# slaveMeteo.net
KiCad netlist of a schematic drawn in EAGLE
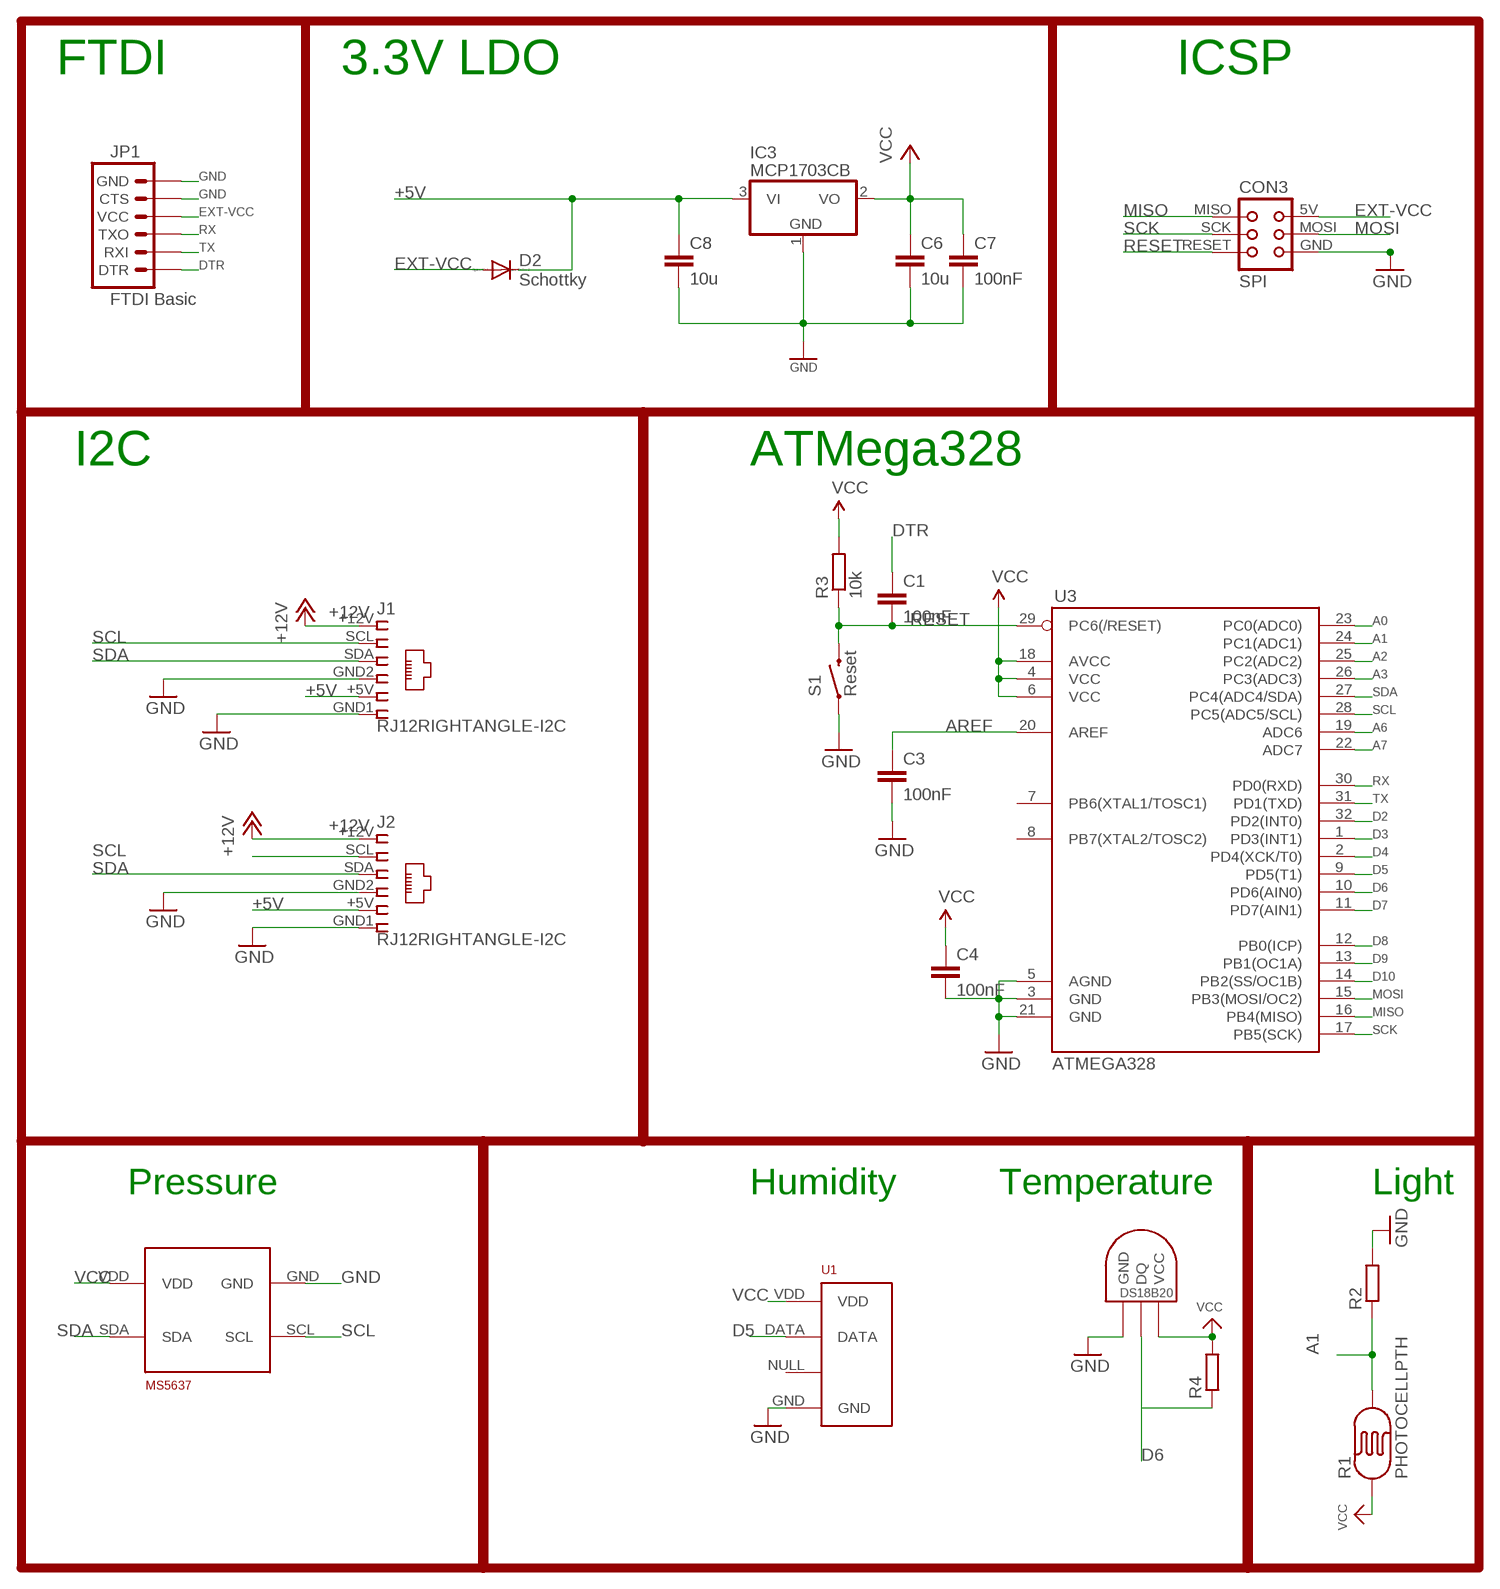
[diagram p0: schematic, sheet 1]

(export (version "E")
  (design (tool "Eeschema 10.0.6"))
  (components
    (comp (ref "C1")
      (value "100nF")
      (footprint "eagle-import:C0805K")
      (fields (field (name "MPN") "80-C1206C104K5R"))
      (libsource (lib "eagle-import") (part "C-EUC0805K"))
    )
    (comp (ref "C3")
      (value "100nF")
      (footprint "eagle-import:C0805K")
      (fields (field (name "MPN") "80-C1206C104K5R"))
      (libsource (lib "eagle-import") (part "C-EUC0805K"))
    )
    (comp (ref "C4")
      (value "100nF")
      (footprint "eagle-import:C0805K")
      (fields (field (name "MPN") "80-C1206C104K5R"))
      (libsource (lib "eagle-import") (part "C-EUC0805K"))
    )
    (comp (ref "C6")
      (value "10u")
      (footprint "eagle-import:C0805K")
      (fields (field (name "MPN") "77-VJ1206V106ZXQTBC"))
      (libsource (lib "eagle-import") (part "C-EUC0805K"))
    )
    (comp (ref "C7")
      (value "100nF")
      (footprint "eagle-import:C0805K")
      (fields (field (name "MPN") "80-C1206C104K5R"))
      (libsource (lib "eagle-import") (part "C-EUC0805K"))
    )
    (comp (ref "C8")
      (value "10u")
      (footprint "eagle-import:C0805K")
      (fields (field (name "MPN") "77-VJ1206V106ZXQTBC"))
      (libsource (lib "eagle-import") (part "C-EUC0805K"))
    )
    (comp (ref "CON3")
      (value "SPI")
      (footprint "eagle-import:TC2030-MCP")
      (libsource (lib "eagle-import") (part "TINYISPTAG"))
    )
    (comp (ref "D2")
      (value "Schottky")
      (footprint "eagle-import:SOD123")
      (fields (field (name "MPN") "621-1N5819HW-F"))
      (libsource (lib "eagle-import") (part "MBR0520LT"))
    )
    (comp (ref "IC3")
      (value "MCP1703CB")
      (footprint "eagle-import:SOT23")
      (libsource (lib "eagle-import") (part "MCP1703CB"))
    )
    (comp (ref "J1")
      (value "RJ12RIGHTANGLE-I2C")
      (footprint "eagle-import:RJ12-RIGHTANGLE-I2C")
      (libsource (lib "eagle-import") (part "RJ12RIGHTANGLE-I2C"))
    )
    (comp (ref "J2")
      (value "RJ12RIGHTANGLE-I2C")
      (footprint "eagle-import:RJ12-RIGHTANGLE-I2C")
      (libsource (lib "eagle-import") (part "RJ12RIGHTANGLE-I2C"))
    )
    (comp (ref "JP1")
      (value "FTDI Basic")
      (footprint "eagle-import:1X06")
      (libsource (lib "eagle-import") (part "ARDUINO_SERIAL_PROGRAMPTH"))
    )
    (comp (ref "R1")
      (value "PHOTOCELLPTH")
      (footprint "eagle-import:PHOTOCELL")
      (libsource (lib "eagle-import") (part "PHOTOCELLPTH"))
    )
    (comp (ref "R2")
      (value "R-EU_R0805")
      (footprint "eagle-import:R0805")
      (libsource (lib "eagle-import") (part "resistor_348_R-EU_R0805"))
    )
    (comp (ref "R3")
      (value "10k")
      (footprint "eagle-import:R0805")
      (libsource (lib "eagle-import") (part "R-EU_R0805"))
    )
    (comp (ref "R4")
      (value "R-EU_R0805")
      (footprint "eagle-import:R0805")
      (libsource (lib "eagle-import") (part "resistor_348_R-EU_R0805"))
    )
    (comp (ref "S1")
      (value "Reset")
      (footprint "eagle-import:TACTILE-SWITCH-SMD-ALT01")
      (libsource (lib "eagle-import") (part "SWITCH-MOMENTARY-2SMD-ALT01"))
    )
    (comp (ref "U$1")
      (value "DS1820TO92")
      (footprint "eagle-import:DS1820")
      (libsource (lib "eagle-import") (part "DS1820TO92"))
    )
    (comp (ref "U$19")
      (value "MS5637")
      (footprint "eagle-import:MS5637")
      (libsource (lib "eagle-import") (part "MS5637"))
    )
    (comp (ref "U1")
      (value "RHT03_DHT-22_AM2302RA")
      (footprint "eagle-import:RHT03_DHT-22_RA")
      (libsource (lib "eagle-import") (part "RHT03_DHT-22_AM2302RA"))
    )
    (comp (ref "U3")
      (value "ATMEGA328")
      (footprint "eagle-import:TQFP32-08")
      (libsource (lib "eagle-import") (part "ATMEGA168"))
    )
  )
  (nets
    (net (code "1") (name "+12V") (class "Default")
      (node (ref "J1") (pin "+12V") (pinfunction "1_+12V") (pintype "bidirectional"))
      (node (ref "J2") (pin "+12V") (pinfunction "1_+12V") (pintype "bidirectional"))
    )
    (net (code "2") (name "/+5V") (class "Default")
      (node (ref "C8") (pin "1") (pinfunction "1_1") (pintype "passive"))
      (node (ref "D2") (pin "C") (pinfunction "C_C") (pintype "passive"))
      (node (ref "IC3") (pin "3") (pinfunction "VI_3") (pintype "input"))
      (node (ref "J1") (pin "+5V") (pinfunction "5_+5V") (pintype "bidirectional"))
      (node (ref "J2") (pin "+5V") (pinfunction "5_+5V") (pintype "bidirectional"))
    )
    (net (code "3") (name "/A0") (class "Default")
      (node (ref "U3") (pin "23") (pinfunction "PC0(ADC0)_23") (pintype "bidirectional"))
    )
    (net (code "4") (name "/A1") (class "Default")
      (node (ref "R1") (pin "2") (pinfunction "P$2_2") (pintype "bidirectional"))
      (node (ref "R2") (pin "1") (pinfunction "1_1") (pintype "passive"))
      (node (ref "U3") (pin "24") (pinfunction "PC1(ADC1)_24") (pintype "bidirectional"))
    )
    (net (code "5") (name "/A2") (class "Default")
      (node (ref "U3") (pin "25") (pinfunction "PC2(ADC2)_25") (pintype "bidirectional"))
    )
    (net (code "6") (name "/A3") (class "Default")
      (node (ref "U3") (pin "26") (pinfunction "PC3(ADC3)_26") (pintype "bidirectional"))
    )
    (net (code "7") (name "/A6") (class "Default")
      (node (ref "U3") (pin "19") (pinfunction "ADC6_19") (pintype "bidirectional"))
    )
    (net (code "8") (name "/A7") (class "Default")
      (node (ref "U3") (pin "22") (pinfunction "ADC7_22") (pintype "bidirectional"))
    )
    (net (code "9") (name "/AREF") (class "Default")
      (node (ref "C3") (pin "1") (pinfunction "1_1") (pintype "passive"))
      (node (ref "U3") (pin "20") (pinfunction "AREF_20") (pintype "bidirectional"))
    )
    (net (code "10") (name "/D2") (class "Default")
      (node (ref "U3") (pin "32") (pinfunction "PD2(INT0)_32") (pintype "bidirectional"))
    )
    (net (code "11") (name "/D3") (class "Default")
      (node (ref "U3") (pin "1") (pinfunction "PD3(INT1)_1") (pintype "bidirectional"))
    )
    (net (code "12") (name "/D4") (class "Default")
      (node (ref "U3") (pin "2") (pinfunction "PD4(XCK/T0)_2") (pintype "bidirectional"))
    )
    (net (code "13") (name "/D5") (class "Default")
      (node (ref "U1") (pin "DATA") (pinfunction "DATA_DATA") (pintype "bidirectional"))
      (node (ref "U3") (pin "9") (pinfunction "PD5(T1)_9") (pintype "bidirectional"))
    )
    (net (code "14") (name "/D6") (class "Default")
      (node (ref "R4") (pin "1") (pinfunction "1_1") (pintype "passive"))
      (node (ref "U$1") (pin "DQ") (pinfunction "DQ_DQ") (pintype "bidirectional"))
      (node (ref "U3") (pin "10") (pinfunction "PD6(AIN0)_10") (pintype "bidirectional"))
    )
    (net (code "15") (name "/D7") (class "Default")
      (node (ref "U3") (pin "11") (pinfunction "PD7(AIN1)_11") (pintype "bidirectional"))
    )
    (net (code "16") (name "/D8") (class "Default")
      (node (ref "U3") (pin "12") (pinfunction "PB0(ICP)_12") (pintype "bidirectional"))
    )
    (net (code "17") (name "/D9") (class "Default")
      (node (ref "U3") (pin "13") (pinfunction "PB1(OC1A)_13") (pintype "bidirectional"))
    )
    (net (code "18") (name "/D10") (class "Default")
      (node (ref "U3") (pin "14") (pinfunction "PB2(SS/OC1B)_14") (pintype "bidirectional"))
    )
    (net (code "19") (name "/DTR") (class "Default")
      (node (ref "C1") (pin "1") (pinfunction "1_1") (pintype "passive"))
      (node (ref "JP1") (pin "1") (pinfunction "DTR_1") (pintype "passive"))
    )
    (net (code "20") (name "/EXT-VCC") (class "Default")
      (node (ref "CON3") (pin "5V") (pinfunction "VCC_5V") (pintype "passive"))
      (node (ref "D2") (pin "A") (pinfunction "A_A") (pintype "passive"))
      (node (ref "JP1") (pin "4") (pinfunction "VCC_4") (pintype "passive"))
    )
    (net (code "21") (name "/MISO") (class "Default")
      (node (ref "CON3") (pin "MISO") (pinfunction "MISO_MISO") (pintype "passive"))
      (node (ref "U3") (pin "16") (pinfunction "PB4(MISO)_16") (pintype "bidirectional"))
    )
    (net (code "22") (name "/MOSI") (class "Default")
      (node (ref "CON3") (pin "MOSI") (pinfunction "MOSI_MOSI") (pintype "passive"))
      (node (ref "U3") (pin "15") (pinfunction "PB3(MOSI/OC2)_15") (pintype "bidirectional"))
    )
    (net (code "23") (name "/RESET") (class "Default")
      (node (ref "C1") (pin "2") (pinfunction "2_2") (pintype "passive"))
      (node (ref "CON3") (pin "RESET") (pinfunction "RESET_RESET") (pintype "passive"))
      (node (ref "R3") (pin "1") (pinfunction "1_1") (pintype "passive"))
      (node (ref "S1") (pin "3") (pinfunction "2_3") (pintype "passive"))
      (node (ref "S1") (pin "4") (pinfunction "2_4") (pintype "passive"))
      (node (ref "U3") (pin "29") (pinfunction "PC6(/RESET)_29") (pintype "bidirectional"))
    )
    (net (code "24") (name "/RX") (class "Default")
      (node (ref "JP1") (pin "3") (pinfunction "TXO_3") (pintype "passive"))
      (node (ref "U3") (pin "30") (pinfunction "PD0(RXD)_30") (pintype "bidirectional"))
    )
    (net (code "25") (name "/SCK") (class "Default")
      (node (ref "CON3") (pin "SCK") (pinfunction "SCK_SCK") (pintype "passive"))
      (node (ref "U3") (pin "17") (pinfunction "PB5(SCK)_17") (pintype "bidirectional"))
    )
    (net (code "26") (name "/SCL") (class "Default")
      (node (ref "J1") (pin "SCL") (pinfunction "2_SCL") (pintype "bidirectional"))
      (node (ref "J2") (pin "SCL") (pinfunction "2_SCL") (pintype "bidirectional"))
      (node (ref "U$19") (pin "SCL") (pinfunction "SCL_SCL") (pintype "bidirectional"))
      (node (ref "U3") (pin "28") (pinfunction "PC5(ADC5/SCL)_28") (pintype "bidirectional"))
    )
    (net (code "27") (name "/SDA") (class "Default")
      (node (ref "J1") (pin "SDA") (pinfunction "3_SDA") (pintype "bidirectional"))
      (node (ref "J2") (pin "SDA") (pinfunction "3_SDA") (pintype "bidirectional"))
      (node (ref "U$19") (pin "SDA") (pinfunction "SDA_SDA") (pintype "bidirectional"))
      (node (ref "U3") (pin "27") (pinfunction "PC4(ADC4/SDA)_27") (pintype "bidirectional"))
    )
    (net (code "28") (name "/TX") (class "Default")
      (node (ref "JP1") (pin "2") (pinfunction "RXI_2") (pintype "passive"))
      (node (ref "U3") (pin "31") (pinfunction "PD1(TXD)_31") (pintype "bidirectional"))
    )
    (net (code "29") (name "GND") (class "Default")
      (node (ref "C3") (pin "2") (pinfunction "2_2") (pintype "passive"))
      (node (ref "C4") (pin "2") (pinfunction "2_2") (pintype "passive"))
      (node (ref "C6") (pin "2") (pinfunction "2_2") (pintype "passive"))
      (node (ref "C7") (pin "2") (pinfunction "2_2") (pintype "passive"))
      (node (ref "C8") (pin "2") (pinfunction "2_2") (pintype "passive"))
      (node (ref "CON3") (pin "GND") (pinfunction "GND_GND") (pintype "passive"))
      (node (ref "IC3") (pin "1") (pinfunction "GND_1") (pintype "passive"))
      (node (ref "J1") (pin "GND1") (pinfunction "6_GND1") (pintype "bidirectional"))
      (node (ref "J1") (pin "GND2") (pinfunction "4_GND2") (pintype "bidirectional"))
      (node (ref "J2") (pin "GND1") (pinfunction "6_GND1") (pintype "bidirectional"))
      (node (ref "J2") (pin "GND2") (pinfunction "4_GND2") (pintype "bidirectional"))
      (node (ref "JP1") (pin "5") (pinfunction "CTS_5") (pintype "passive"))
      (node (ref "JP1") (pin "6") (pinfunction "GND_6") (pintype "passive"))
      (node (ref "R2") (pin "2") (pinfunction "2_2") (pintype "passive"))
      (node (ref "S1") (pin "1") (pinfunction "1_1") (pintype "passive"))
      (node (ref "S1") (pin "2") (pinfunction "1_2") (pintype "passive"))
      (node (ref "U$1") (pin "GND") (pinfunction "GND_GND") (pintype "power_in"))
      (node (ref "U$19") (pin "GND") (pinfunction "GND_GND") (pintype "bidirectional"))
      (node (ref "U1") (pin "GND") (pinfunction "GND_GND") (pintype "power_in"))
      (node (ref "U3") (pin "21") (pinfunction "GND_21") (pintype "bidirectional"))
      (node (ref "U3") (pin "3") (pinfunction "GND_3") (pintype "bidirectional"))
      (node (ref "U3") (pin "5") (pinfunction "AGND_5") (pintype "bidirectional"))
    )
    (net (code "30") (name "VCC") (class "Default")
      (node (ref "C4") (pin "1") (pinfunction "1_1") (pintype "passive"))
      (node (ref "C6") (pin "1") (pinfunction "1_1") (pintype "passive"))
      (node (ref "C7") (pin "1") (pinfunction "1_1") (pintype "passive"))
      (node (ref "IC3") (pin "2") (pinfunction "VO_2") (pintype "passive"))
      (node (ref "R1") (pin "1") (pinfunction "P$1_1") (pintype "bidirectional"))
      (node (ref "R3") (pin "2") (pinfunction "2_2") (pintype "passive"))
      (node (ref "R4") (pin "2") (pinfunction "2_2") (pintype "passive"))
      (node (ref "U$1") (pin "VDD") (pinfunction "VCC_VDD") (pintype "power_in"))
      (node (ref "U$19") (pin "VDD") (pinfunction "VDD_VDD") (pintype "bidirectional"))
      (node (ref "U1") (pin "VDD") (pinfunction "VDD_VDD") (pintype "power_in"))
      (node (ref "U3") (pin "18") (pinfunction "AVCC_18") (pintype "bidirectional"))
      (node (ref "U3") (pin "4") (pinfunction "VCC_4") (pintype "bidirectional"))
      (node (ref "U3") (pin "6") (pinfunction "VCC_6") (pintype "bidirectional"))
    )
    (net (code "31") (name "unconnected-(U1-PadNULL)") (class "Default")
      (node (ref "U1") (pin "NULL") (pinfunction "NULL_NULL") (pintype "no_connect"))
    )
    (net (code "32") (name "unconnected-(U3-PB6(XTAL1{slash}TOSC1)-Pad7)") (class "Default")
      (node (ref "U3") (pin "7") (pinfunction "PB6(XTAL1/TOSC1)_7") (pintype "bidirectional"))
    )
    (net (code "33") (name "unconnected-(U3-PB7(XTAL2{slash}TOSC2)-Pad8)") (class "Default")
      (node (ref "U3") (pin "8") (pinfunction "PB7(XTAL2/TOSC2)_8") (pintype "bidirectional"))
    )
  )
)
